# untitled.net
KiCad netlist of a schematic drawn in EAGLE
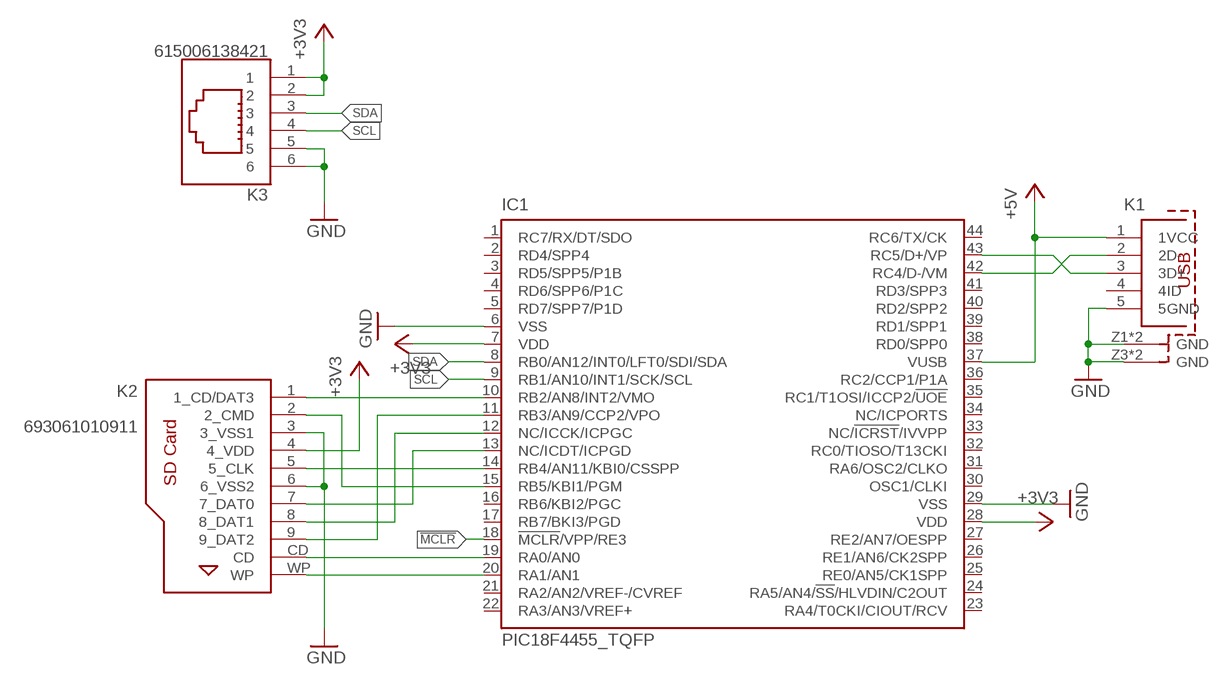
[diagram p0: schematic, sheet 1]

(export (version "E")
  (design (tool "Eeschema 10.0.6"))
  (components
    (comp (ref "IC1")
      (value "PIC18F4455_TQFP")
      (footprint "eagle-import:TQFP44")
      (fields (field (name "MF") "MICROCHIP") (field (name "MPN") "PIC18F4455-I/PT"))
      (libsource (lib "eagle-import") (part "PIC18F4_TQFP455"))
    )
    (comp (ref "K1")
      (value "629105150521")
      (footprint "eagle-import:629105150521")
      (libsource (lib "eagle-import") (part "629105150521"))
    )
    (comp (ref "K2")
      (value "693061010911")
      (footprint "eagle-import:693061010911")
      (libsource (lib "eagle-import") (part "693061010911"))
    )
    (comp (ref "K3")
      (value "615006138421")
      (footprint "eagle-import:615006138421")
      (libsource (lib "eagle-import") (part "615006138421"))
    )
  )
  (nets
    (net (code "1") (name "+3V3") (class "Default")
      (node (ref "IC1") (pin "28") (pinfunction "VDD_28") (pintype "power_in"))
      (node (ref "IC1") (pin "7") (pinfunction "VDD_7") (pintype "power_in"))
      (node (ref "K2") (pin "4") (pinfunction "4_VDD_4") (pintype "bidirectional"))
      (node (ref "K3") (pin "1") (pinfunction "1_1") (pintype "passive"))
      (node (ref "K3") (pin "2") (pinfunction "2_2") (pintype "passive"))
    )
    (net (code "2") (name "+5V") (class "Default")
      (node (ref "IC1") (pin "37") (pinfunction "VUSB_37") (pintype "bidirectional"))
      (node (ref "K1") (pin "1") (pinfunction "1VCC_1") (pintype "passive"))
    )
    (net (code "3") (name "/~{MCLR}") (class "Default")
      (node (ref "IC1") (pin "18") (pinfunction "~{MCLR}/VPP/RE3_18") (pintype "input"))
    )
    (net (code "4") (name "GND") (class "Default")
      (node (ref "IC1") (pin "29") (pinfunction "VSS_29") (pintype "power_in"))
      (node (ref "IC1") (pin "6") (pinfunction "VSS_6") (pintype "power_in"))
      (node (ref "K1") (pin "5") (pinfunction "5GND_5") (pintype "passive"))
      (node (ref "K1") (pin "Z1") (pinfunction "GND_Z1") (pintype "bidirectional"))
      (node (ref "K1") (pin "Z2") (pinfunction "GND_Z2") (pintype "bidirectional"))
      (node (ref "K1") (pin "Z3") (pinfunction "GND_Z3") (pintype "bidirectional"))
      (node (ref "K1") (pin "Z4") (pinfunction "GND_Z4") (pintype "bidirectional"))
      (node (ref "K2") (pin "3") (pinfunction "3_VSS1_3") (pintype "bidirectional"))
      (node (ref "K2") (pin "6") (pinfunction "6_VSS2_6") (pintype "bidirectional"))
      (node (ref "K3") (pin "5") (pinfunction "5_5") (pintype "passive"))
      (node (ref "K3") (pin "6") (pinfunction "6_6") (pintype "passive"))
    )
    (net (code "5") (name "Net-(IC1-NC{slash}ICCK{slash}ICPGC)") (class "Default")
      (node (ref "IC1") (pin "12") (pinfunction "NC/ICCK/ICPGC_12") (pintype "bidirectional"))
      (node (ref "K2") (pin "8") (pinfunction "8_DAT1_8") (pintype "bidirectional"))
    )
    (net (code "6") (name "Net-(IC1-NC{slash}ICDT{slash}ICPGD)") (class "Default")
      (node (ref "IC1") (pin "13") (pinfunction "NC/ICDT/ICPGD_13") (pintype "bidirectional"))
      (node (ref "K2") (pin "7") (pinfunction "7_DAT0_7") (pintype "bidirectional"))
    )
    (net (code "7") (name "Net-(IC1-RA0{slash}AN0)") (class "Default")
      (node (ref "IC1") (pin "19") (pinfunction "RA0/AN0_19") (pintype "bidirectional"))
      (node (ref "K2") (pin "CD") (pinfunction "CD_CD") (pintype "bidirectional"))
    )
    (net (code "8") (name "Net-(IC1-RA1{slash}AN1)") (class "Default")
      (node (ref "IC1") (pin "20") (pinfunction "RA1/AN1_20") (pintype "bidirectional"))
      (node (ref "K2") (pin "WP") (pinfunction "WP_WP") (pintype "bidirectional"))
    )
    (net (code "9") (name "Net-(IC1-RB2{slash}AN8{slash}INT2{slash}VMO)") (class "Default")
      (node (ref "IC1") (pin "10") (pinfunction "RB2/AN8/INT2/VMO_10") (pintype "bidirectional"))
      (node (ref "K2") (pin "1") (pinfunction "1_CD/DAT3_1") (pintype "bidirectional"))
    )
    (net (code "10") (name "Net-(IC1-RB3{slash}AN9{slash}CCP2{slash}VPO)") (class "Default")
      (node (ref "IC1") (pin "11") (pinfunction "RB3/AN9/CCP2/VPO_11") (pintype "bidirectional"))
      (node (ref "K2") (pin "9") (pinfunction "9_DAT2_9") (pintype "bidirectional"))
    )
    (net (code "11") (name "Net-(IC1-RB4{slash}AN11{slash}KBI0{slash}CSSPP)") (class "Default")
      (node (ref "IC1") (pin "14") (pinfunction "RB4/AN11/KBI0/CSSPP_14") (pintype "bidirectional"))
      (node (ref "K2") (pin "5") (pinfunction "5_CLK_5") (pintype "bidirectional"))
    )
    (net (code "12") (name "Net-(IC1-RB5{slash}KBI1{slash}PGM)") (class "Default")
      (node (ref "IC1") (pin "15") (pinfunction "RB5/KBI1/PGM_15") (pintype "bidirectional"))
      (node (ref "K2") (pin "2") (pinfunction "2_CMD_2") (pintype "bidirectional"))
    )
    (net (code "13") (name "Net-(IC1-RC4{slash}D-{slash}VM)") (class "Default")
      (node (ref "IC1") (pin "42") (pinfunction "RC4/D-/VM_42") (pintype "bidirectional"))
      (node (ref "K1") (pin "2") (pinfunction "2D-_2") (pintype "passive"))
    )
    (net (code "14") (name "Net-(IC1-RC5{slash}D+{slash}VP)") (class "Default")
      (node (ref "IC1") (pin "43") (pinfunction "RC5/D+/VP_43") (pintype "bidirectional"))
      (node (ref "K1") (pin "3") (pinfunction "3D+_3") (pintype "passive"))
    )
    (net (code "15") (name "SCL") (class "Default")
      (node (ref "IC1") (pin "9") (pinfunction "RB1/AN10/INT1/SCK/SCL_9") (pintype "bidirectional"))
      (node (ref "K3") (pin "4") (pinfunction "4_4") (pintype "passive"))
    )
    (net (code "16") (name "SDA") (class "Default")
      (node (ref "IC1") (pin "8") (pinfunction "RB0/AN12/INT0/LFT0/SDI/SDA_8") (pintype "bidirectional"))
      (node (ref "K3") (pin "3") (pinfunction "3_3") (pintype "passive"))
    )
    (net (code "17") (name "unconnected-(IC1-NC{slash}ICPORTS-Pad34)") (class "Default")
      (node (ref "IC1") (pin "34") (pinfunction "NC/ICPORTS_34") (pintype "input"))
    )
    (net (code "18") (name "unconnected-(IC1-NC{slash}~{ICRST}{slash}IVVPP-Pad33)") (class "Default")
      (node (ref "IC1") (pin "33") (pinfunction "NC/~{ICRST}/IVVPP_33") (pintype "input"))
    )
    (net (code "19") (name "unconnected-(IC1-OSC1{slash}CLKI-Pad30)") (class "Default")
      (node (ref "IC1") (pin "30") (pinfunction "OSC1/CLKI_30") (pintype "input"))
    )
    (net (code "20") (name "unconnected-(IC1-RA2{slash}AN2{slash}VREF-{slash}CVREF-Pad21)") (class "Default")
      (node (ref "IC1") (pin "21") (pinfunction "RA2/AN2/VREF-/CVREF_21") (pintype "bidirectional"))
    )
    (net (code "21") (name "unconnected-(IC1-RA3{slash}AN3{slash}VREF+-Pad22)") (class "Default")
      (node (ref "IC1") (pin "22") (pinfunction "RA3/AN3/VREF+_22") (pintype "bidirectional"))
    )
    (net (code "22") (name "unconnected-(IC1-RA4{slash}T0CKI{slash}CIOUT{slash}RCV-Pad23)") (class "Default")
      (node (ref "IC1") (pin "23") (pinfunction "RA4/T0CKI/CIOUT/RCV_23") (pintype "bidirectional"))
    )
    (net (code "23") (name "unconnected-(IC1-RA5{slash}AN4{slash}~{SS}{slash}HLVDIN{slash}C2OUT-Pad24)") (class "Default")
      (node (ref "IC1") (pin "24") (pinfunction "RA5/AN4/~{SS}/HLVDIN/C2OUT_24") (pintype "bidirectional"))
    )
    (net (code "24") (name "unconnected-(IC1-RA6{slash}OSC2{slash}CLKO-Pad31)") (class "Default")
      (node (ref "IC1") (pin "31") (pinfunction "RA6/OSC2/CLKO_31") (pintype "output"))
    )
    (net (code "25") (name "unconnected-(IC1-RB6{slash}KBI2{slash}PGC-Pad16)") (class "Default")
      (node (ref "IC1") (pin "16") (pinfunction "RB6/KBI2/PGC_16") (pintype "bidirectional"))
    )
    (net (code "26") (name "unconnected-(IC1-RB7{slash}BKI3{slash}PGD-Pad17)") (class "Default")
      (node (ref "IC1") (pin "17") (pinfunction "RB7/BKI3/PGD_17") (pintype "bidirectional"))
    )
    (net (code "27") (name "unconnected-(IC1-RC0{slash}TIOSO{slash}T13CKI-Pad32)") (class "Default")
      (node (ref "IC1") (pin "32") (pinfunction "RC0/TIOSO/T13CKI_32") (pintype "bidirectional"))
    )
    (net (code "28") (name "unconnected-(IC1-RC1{slash}T1OSI{slash}ICCP2{slash}~{UOE}-Pad35)") (class "Default")
      (node (ref "IC1") (pin "35") (pinfunction "RC1/T1OSI/ICCP2/~{UOE}_35") (pintype "bidirectional"))
    )
    (net (code "29") (name "unconnected-(IC1-RC2{slash}CCP1{slash}P1A-Pad36)") (class "Default")
      (node (ref "IC1") (pin "36") (pinfunction "RC2/CCP1/P1A_36") (pintype "bidirectional"))
    )
    (net (code "30") (name "unconnected-(IC1-RC6{slash}TX{slash}CK-Pad44)") (class "Default")
      (node (ref "IC1") (pin "44") (pinfunction "RC6/TX/CK_44") (pintype "bidirectional"))
    )
    (net (code "31") (name "unconnected-(IC1-RC7{slash}RX{slash}DT{slash}SDO-Pad1)") (class "Default")
      (node (ref "IC1") (pin "1") (pinfunction "RC7/RX/DT/SDO_1") (pintype "bidirectional"))
    )
    (net (code "32") (name "unconnected-(IC1-RD0{slash}SPP0-Pad38)") (class "Default")
      (node (ref "IC1") (pin "38") (pinfunction "RD0/SPP0_38") (pintype "bidirectional"))
    )
    (net (code "33") (name "unconnected-(IC1-RD1{slash}SPP1-Pad39)") (class "Default")
      (node (ref "IC1") (pin "39") (pinfunction "RD1/SPP1_39") (pintype "bidirectional"))
    )
    (net (code "34") (name "unconnected-(IC1-RD2{slash}SPP2-Pad40)") (class "Default")
      (node (ref "IC1") (pin "40") (pinfunction "RD2/SPP2_40") (pintype "bidirectional"))
    )
    (net (code "35") (name "unconnected-(IC1-RD3{slash}SPP3-Pad41)") (class "Default")
      (node (ref "IC1") (pin "41") (pinfunction "RD3/SPP3_41") (pintype "bidirectional"))
    )
    (net (code "36") (name "unconnected-(IC1-RD4{slash}SPP4-Pad2)") (class "Default")
      (node (ref "IC1") (pin "2") (pinfunction "RD4/SPP4_2") (pintype "bidirectional"))
    )
    (net (code "37") (name "unconnected-(IC1-RD5{slash}SPP5{slash}P1B-Pad3)") (class "Default")
      (node (ref "IC1") (pin "3") (pinfunction "RD5/SPP5/P1B_3") (pintype "bidirectional"))
    )
    (net (code "38") (name "unconnected-(IC1-RD6{slash}SPP6{slash}P1C-Pad4)") (class "Default")
      (node (ref "IC1") (pin "4") (pinfunction "RD6/SPP6/P1C_4") (pintype "bidirectional"))
    )
    (net (code "39") (name "unconnected-(IC1-RD7{slash}SPP7{slash}P1D-Pad5)") (class "Default")
      (node (ref "IC1") (pin "5") (pinfunction "RD7/SPP7/P1D_5") (pintype "bidirectional"))
    )
    (net (code "40") (name "unconnected-(IC1-RE0{slash}AN5{slash}CK1SPP-Pad25)") (class "Default")
      (node (ref "IC1") (pin "25") (pinfunction "RE0/AN5/CK1SPP_25") (pintype "bidirectional"))
    )
    (net (code "41") (name "unconnected-(IC1-RE1{slash}AN6{slash}CK2SPP-Pad26)") (class "Default")
      (node (ref "IC1") (pin "26") (pinfunction "RE1/AN6/CK2SPP_26") (pintype "bidirectional"))
    )
    (net (code "42") (name "unconnected-(IC1-RE2{slash}AN7{slash}OESPP-Pad27)") (class "Default")
      (node (ref "IC1") (pin "27") (pinfunction "RE2/AN7/OESPP_27") (pintype "bidirectional"))
    )
    (net (code "43") (name "unconnected-(K1-4ID-Pad4)") (class "Default")
      (node (ref "K1") (pin "4") (pinfunction "4ID_4") (pintype "passive"))
    )
  )
)
